# Power_Distribution_2021_5V.net
KiCad netlist of a schematic drawn in Altium Designer
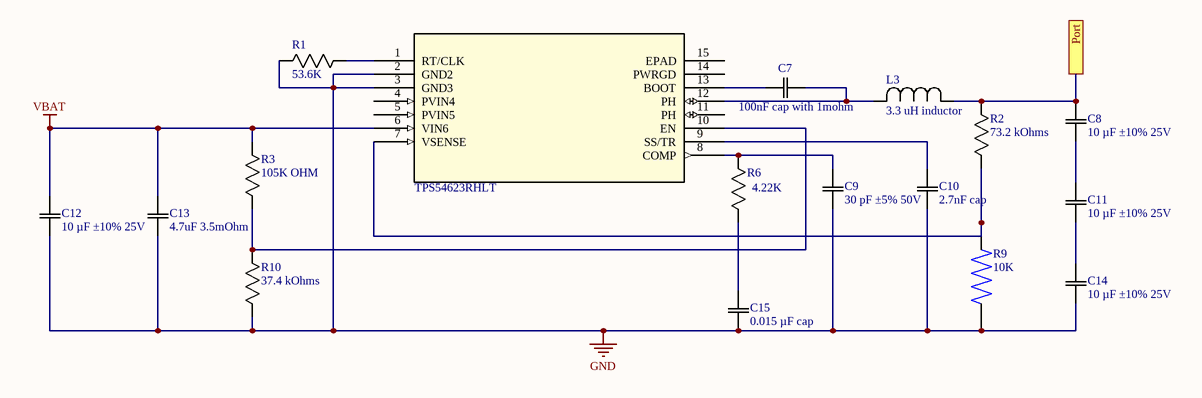
[diagram p0: Power_Distribution_2021_5V.SchDoc]

(export (version "E")
  (design (tool "Eeschema 10.0.6"))
  (components
    (comp (ref "*")
      (value "TPS54623RHLT")
      (description "Conv DC-DC 4.5V to 17V Synchronous Step Down Single-Out 0.6V to 15V 6A 14-Pin VQFN EP T/R")
      (fields (field (name "MANUFACTURER") "Texas Instruments"))
      (libsource (lib "Power_Distribution") (part "TPS54623RHLT"))
    )
    (comp (ref "C7")
      (value "100nF cap with 1mohm")
      (fields
        (field (name "MANUFACTURER") "KEMET")
        (field (name "MANUFACTURER PART NUMBER") "C0603C104Z3VACTU")
        (field (name "TOLERANCE") "80%")
      )
      (libsource (lib "Power_Distribution") (part "C0603C104Z3VACTU"))
    )
    (comp (ref "C8")
      (value "10 µF ±10% 25V")
      (fields
        (field (name "MANUFACTURER") "Murata")
        (field (name "MANUFACTURER PART NUMBER") "GRM31CR71E106KA12L")
        (field (name "TOLERANCE") "10%")
      )
      (libsource (lib "Power_Distribution") (part "GRM31CR71E106KA12L"))
    )
    (comp (ref "C9")
      (value "30 pF ±5% 50V")
      (description "Cap Ceramic 30pF 50V C0G 5% Pad SMD 0805 125C T/R")
      (fields
        (field (name "MANUFACTURER") "Samsung")
        (field (name "MANUFACTURER PART NUMBER") "CL21C300JBANNNC")
      )
      (libsource (lib "Power_Distribution") (part "CL21C300JBANNNC"))
    )
    (comp (ref "C10")
      (value "2.7nF cap")
      (description "Cap Ceramic 0.0027uF 50V C0G 5% SMD 0805 125C Paper T/R")
      (fields
        (field (name "MANUFACTURER") "TDK")
        (field (name "MANUFACTURER PART NUMBER") "C2012C0G1H272J060AA")
      )
      (libsource (lib "Power_Distribution") (part "C2012C0G1H272J060AA"))
    )
    (comp (ref "C11")
      (value "10 µF ±10% 25V")
      (fields
        (field (name "MANUFACTURER") "Murata")
        (field (name "MANUFACTURER PART NUMBER") "GRM31CR71E106KA12L")
        (field (name "TOLERANCE") "10%")
      )
      (libsource (lib "Power_Distribution") (part "GRM31CR71E106KA12L"))
    )
    (comp (ref "C12")
      (value "10 µF ±10% 25V")
      (fields
        (field (name "MANUFACTURER") "Murata")
        (field (name "MANUFACTURER PART NUMBER") "GRM31CR71E106KA12L")
        (field (name "TOLERANCE") "10%")
      )
      (libsource (lib "Power_Distribution") (part "GRM31CR71E106KA12L"))
    )
    (comp (ref "C13")
      (value "4.7uF 3.5mOhm")
      (description "1206 4.7 uF 50 V ±10% Tolerance X7R SMT Multilayer Ceramic Capacitor")
      (fields
        (field (name "MANUFACTURER") "Murata")
        (field (name "MANUFACTURER PART NUMBER") "GRM31CR71H475KA12L")
      )
      (libsource (lib "Power_Distribution") (part "GRM31CR71H475KA12L"))
    )
    (comp (ref "C14")
      (value "10 µF ±10% 25V")
      (fields
        (field (name "MANUFACTURER") "Murata")
        (field (name "MANUFACTURER PART NUMBER") "GRM31CR71E106KA12L")
        (field (name "TOLERANCE") "10%")
      )
      (libsource (lib "Power_Distribution") (part "GRM31CR71E106KA12L"))
    )
    (comp (ref "C15")
      (value "0.015 µF cap")
      (fields
        (field (name "MANUFACTURER") "TDK")
        (field (name "MANUFACTURER PART NUMBER") "CGA4F2C0G1H153J085AA")
        (field (name "TOLERANCE") "5%")
      )
      (libsource (lib "Power_Distribution") (part "CGA4F2C0G1H153J085AA"))
    )
    (comp (ref "L3")
      (value "3.3 uH inductor")
      (description "Inductor High Current Shielded Wirewound 3.3uH 20% 100KHz 10A 11.8mOhm DCR 4040 T/R")
      (fields
        (field (name "MANUFACTURER") "Vishay Dale")
        (field (name "MANUFACTURER PART NUMBER") "IHLP4040DZER3R3M01")
      )
      (libsource (lib "Power_Distribution") (part "IHLP4040DZER3R3M01"))
    )
    (comp (ref "R1")
      (value "53.6K")
      (description "Res Thick Film 0603 53.6K Ohm 1% 0.1W(1/10W) ±100ppm/°C Pad SMD T/R")
      (fields
        (field (name "MANUFACTURER") "Yageo")
        (field (name "MANUFACTURER PART NUMBER") "RC0603FR-0753K6L")
      )
      (libsource (lib "Power_Distribution") (part "RC0603FR-0753K6L"))
    )
    (comp (ref "R2")
      (value "73.2 kOhms")
      (description "YAGEO - RC0603FR-0773K2L - Resistor")
      (fields
        (field (name "MANUFACTURER") "Yageo")
        (field (name "MANUFACTURER PART NUMBER") "RC0603FR-0773K2L")
      )
      (libsource (lib "Power_Distribution") (part "RC0603FR-0773K2L"))
    )
    (comp (ref "R3")
      (value "105K OHM")
      (description "Thick Film Resistors 105K OHM 1%")
      (fields
        (field (name "MANUFACTURER") "Yageo")
        (field (name "MANUFACTURER PART NUMBER") "RC0603FR-07105KL")
      )
      (libsource (lib "Power_Distribution") (part "RC0603FR-07105KL"))
    )
    (comp (ref "R6")
      (value "4.22K")
      (fields
        (field (name "MANUFACTURER") "Yageo")
        (field (name "MANUFACTURER PART NUMBER") "RC0603FR-074K22L")
        (field (name "TOLERANCE") "1%")
      )
      (libsource (lib "Power_Distribution") (part "RC0603FR-074K22L"))
    )
    (comp (ref "R9")
      (value "10K")
      (footprint "RESC3216X65N:RESC3216X65N")
      (description "Res Thin Film 1206 10K Ohm 0.1% 0.25W(1/4W) ?25ppm/C Molded SMD T/R")
      (fields (field (name "MP") "TNPW120610K0BETA"))
      (libsource (lib "Power_Distribution") (part "TNPW120610K0BETA"))
    )
    (comp (ref "R10")
      (value "37.4 kOhms")
      (description "YAGEO - RC0603FR-0737K4L - Resistor")
      (fields
        (field (name "MANUFACTURER") "Yageo")
        (field (name "MANUFACTURER PART NUMBER") "RC0603FR-0737K4L")
      )
      (libsource (lib "Power_Distribution") (part "RC0603FR-0737K4L"))
    )
  )
  (nets
    (net (code "1") (name "/Port") (class "Default")
      (node (ref "C8") (pin "2") (pinfunction "2_2") (pintype "passive"))
      (node (ref "L3") (pin "1") (pinfunction "1_1") (pintype "passive"))
      (node (ref "R2") (pin "1") (pinfunction "1_1") (pintype "passive"))
    )
    (net (code "2") (name "GND") (class "Default")
      (node (ref "*") (pin "2") (pinfunction "GND2_2") (pintype "power_in"))
      (node (ref "*") (pin "3") (pinfunction "GND3_3") (pintype "power_in"))
      (node (ref "C10") (pin "1") (pinfunction "1_1") (pintype "passive"))
      (node (ref "C12") (pin "1") (pinfunction "1_1") (pintype "passive"))
      (node (ref "C13") (pin "1") (pinfunction "1_1") (pintype "passive"))
      (node (ref "C14") (pin "1") (pinfunction "1_1") (pintype "passive"))
      (node (ref "C15") (pin "1") (pinfunction "1_1") (pintype "passive"))
      (node (ref "C9") (pin "1") (pinfunction "1_1") (pintype "passive"))
      (node (ref "R1") (pin "1") (pinfunction "1_1") (pintype "passive"))
      (node (ref "R10") (pin "2") (pinfunction "2_2") (pintype "passive"))
      (node (ref "R9") (pin "1") (pinfunction "1_1") (pintype "passive"))
    )
    (net (code "3") (name "Net-(*-BOOT)") (class "Default")
      (node (ref "*") (pin "13") (pinfunction "BOOT_13") (pintype "passive"))
      (node (ref "C7") (pin "1") (pinfunction "1_1") (pintype "passive"))
    )
    (net (code "4") (name "Net-(*-COMP)") (class "Default")
      (node (ref "*") (pin "8") (pinfunction "COMP_8") (pintype "output"))
      (node (ref "C9") (pin "2") (pinfunction "2_2") (pintype "passive"))
      (node (ref "R6") (pin "1") (pinfunction "1_1") (pintype "passive"))
    )
    (net (code "5") (name "Net-(*-EN)") (class "Default")
      (node (ref "*") (pin "10") (pinfunction "EN_10") (pintype "passive"))
      (node (ref "R10") (pin "1") (pinfunction "1_1") (pintype "passive"))
      (node (ref "R3") (pin "2") (pinfunction "2_2") (pintype "passive"))
    )
    (net (code "6") (name "Net-(*-PH-Pad12)") (class "Default")
      (node (ref "*") (pin "12") (pinfunction "PH_12") (pintype "bidirectional"))
      (node (ref "C7") (pin "2") (pinfunction "2_2") (pintype "passive"))
      (node (ref "L3") (pin "2") (pinfunction "2_2") (pintype "passive"))
    )
    (net (code "7") (name "Net-(*-RT{slash}CLK)") (class "Default")
      (node (ref "*") (pin "1") (pinfunction "RT/CLK_1") (pintype "passive"))
      (node (ref "R1") (pin "2") (pinfunction "2_2") (pintype "passive"))
    )
    (net (code "8") (name "Net-(*-SS{slash}TR)") (class "Default")
      (node (ref "*") (pin "9") (pinfunction "SS/TR_9") (pintype "passive"))
      (node (ref "C10") (pin "2") (pinfunction "2_2") (pintype "passive"))
    )
    (net (code "9") (name "Net-(*-VSENSE)") (class "Default")
      (node (ref "*") (pin "7") (pinfunction "VSENSE_7") (pintype "input"))
      (node (ref "R2") (pin "2") (pinfunction "2_2") (pintype "passive"))
      (node (ref "R9") (pin "2") (pinfunction "2_2") (pintype "passive"))
    )
    (net (code "10") (name "Net-(C11-Pad1)") (class "Default")
      (node (ref "C11") (pin "1") (pinfunction "1_1") (pintype "passive"))
      (node (ref "C14") (pin "2") (pinfunction "2_2") (pintype "passive"))
    )
    (net (code "11") (name "Net-(C11-Pad2)") (class "Default")
      (node (ref "C11") (pin "2") (pinfunction "2_2") (pintype "passive"))
      (node (ref "C8") (pin "1") (pinfunction "1_1") (pintype "passive"))
    )
    (net (code "12") (name "Net-(C15-Pad2)") (class "Default")
      (node (ref "C15") (pin "2") (pinfunction "2_2") (pintype "passive"))
      (node (ref "R6") (pin "2") (pinfunction "2_2") (pintype "passive"))
    )
    (net (code "13") (name "VBAT") (class "Default")
      (node (ref "*") (pin "6") (pinfunction "VIN6_6") (pintype "input"))
      (node (ref "C12") (pin "2") (pinfunction "2_2") (pintype "passive"))
      (node (ref "C13") (pin "2") (pinfunction "2_2") (pintype "passive"))
      (node (ref "R3") (pin "1") (pinfunction "1_1") (pintype "passive"))
    )
    (net (code "14") (name "unconnected-(*-EPAD-Pad15)") (class "Default")
      (node (ref "*") (pin "15") (pinfunction "EPAD_15") (pintype "passive"))
    )
    (net (code "15") (name "unconnected-(*-PH-Pad11)") (class "Default")
      (node (ref "*") (pin "11") (pinfunction "PH_11") (pintype "bidirectional"))
    )
    (net (code "16") (name "unconnected-(*-PVIN4-Pad4)") (class "Default")
      (node (ref "*") (pin "4") (pinfunction "PVIN4_4") (pintype "input"))
    )
    (net (code "17") (name "unconnected-(*-PVIN5-Pad5)") (class "Default")
      (node (ref "*") (pin "5") (pinfunction "PVIN5_5") (pintype "input"))
    )
    (net (code "18") (name "unconnected-(*-PWRGD-Pad14)") (class "Default")
      (node (ref "*") (pin "14") (pinfunction "PWRGD_14") (pintype "power_in"))
    )
  )
)
